# obc-v2_TMP-eMMC.net
KiCad netlist of a schematic drawn in Altium Designer
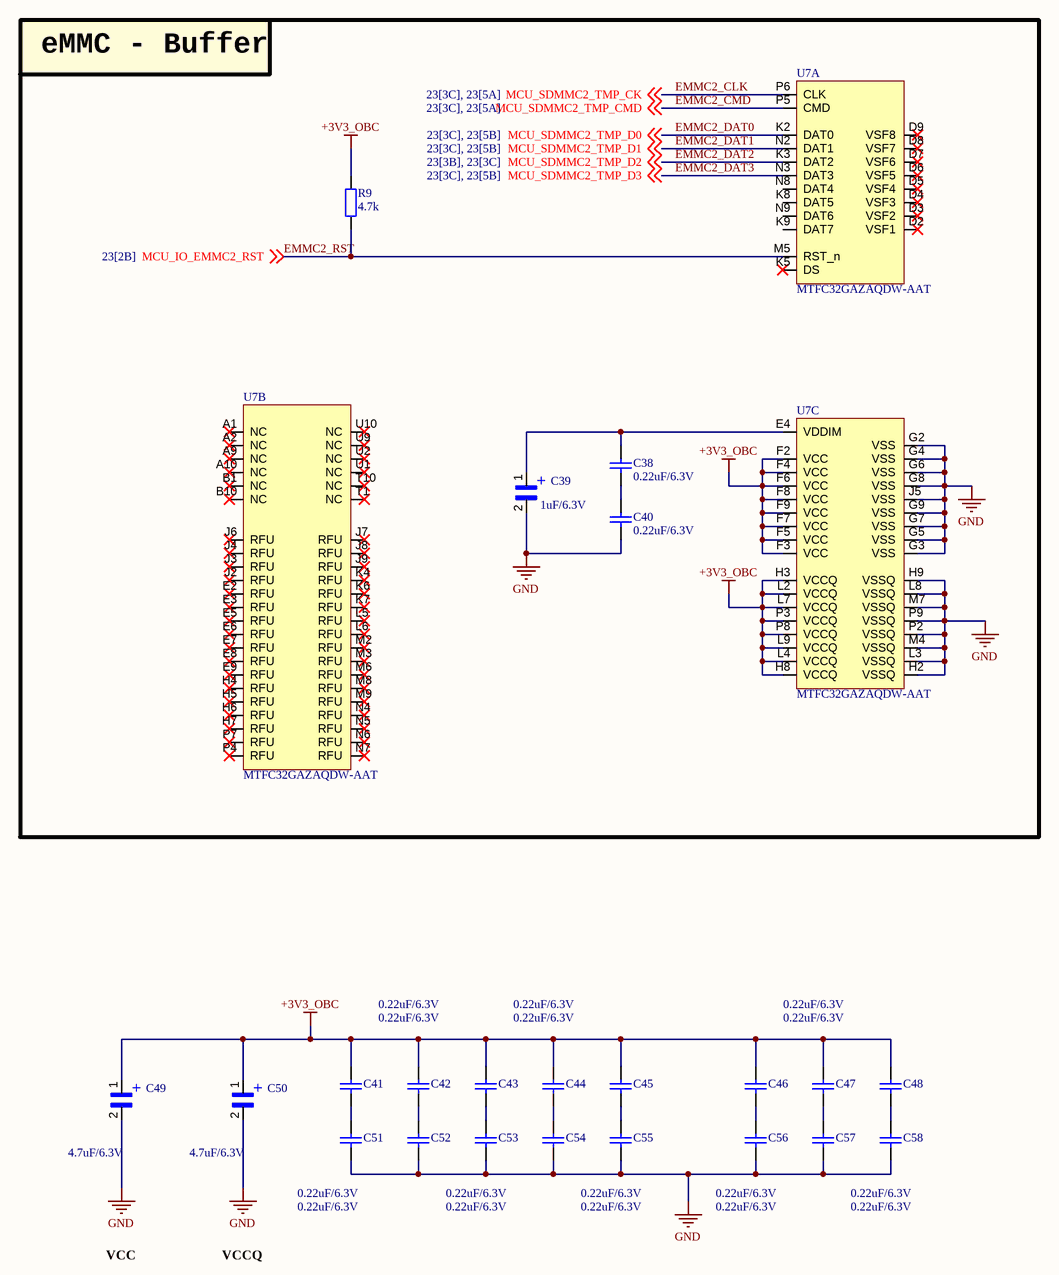
[diagram p0: obc-v2_TMP-eMMC.SchDoc]

(export (version "E")
  (design (tool "Eeschema 10.0.6"))
  (components
    (comp (ref "C38")
      (value "0.22uF/6.3V")
      (footprint "CAP_C_1005X60")
      (description "CAPC")
      (libsource (lib "Altium_Lib_by_KhueNguyenCreator") (part "Tu 0402 33nF 10V"))
    )
    (comp (ref "C39")
      (value "1uF/6.3V")
      (footprint "CAP_MP_1608X90")
      (description "CAPP")
      (fields (field (name "MP") "TACL335M003RTA"))
      (libsource (lib "TACL335M003RTA") (part "TACL335M003RTA"))
    )
    (comp (ref "C40")
      (value "0.22uF/6.3V")
      (footprint "CAP_C_1005X60")
      (description "CAPC")
      (libsource (lib "Altium_Lib_by_KhueNguyenCreator") (part "Tu 0402 33nF 10V"))
    )
    (comp (ref "C41")
      (value "0.22uF/6.3V")
      (footprint "CAP_C_1005X60")
      (description "CAPC")
      (libsource (lib "Altium_Lib_by_KhueNguyenCreator") (part "Tu 0402 33nF 10V"))
    )
    (comp (ref "C42")
      (value "0.22uF/6.3V")
      (footprint "CAP_C_1005X60")
      (description "CAPC")
      (libsource (lib "Altium_Lib_by_KhueNguyenCreator") (part "Tu 0402 33nF 10V"))
    )
    (comp (ref "C43")
      (value "0.22uF/6.3V")
      (footprint "CAP_C_1005X60")
      (description "CAPC")
      (libsource (lib "Altium_Lib_by_KhueNguyenCreator") (part "Tu 0402 33nF 10V"))
    )
    (comp (ref "C44")
      (value "0.22uF/6.3V")
      (footprint "CAP_C_1005X60")
      (description "CAPC")
      (libsource (lib "Altium_Lib_by_KhueNguyenCreator") (part "Tu 0402 33nF 10V"))
    )
    (comp (ref "C45")
      (value "0.22uF/6.3V")
      (footprint "CAP_C_1005X60")
      (description "CAPC")
      (libsource (lib "Altium_Lib_by_KhueNguyenCreator") (part "Tu 0402 33nF 10V"))
    )
    (comp (ref "C46")
      (value "0.22uF/6.3V")
      (footprint "CAP_C_1005X60")
      (description "CAPC")
      (libsource (lib "Altium_Lib_by_KhueNguyenCreator") (part "Tu 0402 33nF 10V"))
    )
    (comp (ref "C47")
      (value "0.22uF/6.3V")
      (footprint "CAP_C_1005X60")
      (description "CAPC")
      (libsource (lib "Altium_Lib_by_KhueNguyenCreator") (part "Tu 0402 33nF 10V"))
    )
    (comp (ref "C48")
      (value "0.22uF/6.3V")
      (footprint "CAP_C_1005X60")
      (description "CAPC")
      (libsource (lib "Altium_Lib_by_KhueNguyenCreator") (part "Tu 0402 33nF 10V"))
    )
    (comp (ref "C49")
      (value "4.7uF/6.3V")
      (footprint "CAP_MP_1608X90")
      (description "CAPP")
      (fields (field (name "MP") "TACL335M003RTA"))
      (libsource (lib "TACL335M003RTA") (part "TACL335M003RTA"))
    )
    (comp (ref "C50")
      (value "4.7uF/6.3V")
      (footprint "CAP_MP_1608X90")
      (description "CAPP")
      (fields (field (name "MP") "TACL335M003RTA"))
      (libsource (lib "TACL335M003RTA") (part "TACL335M003RTA"))
    )
    (comp (ref "C51")
      (value "0.22uF/6.3V")
      (footprint "CAP_C_1005X60")
      (description "CAPC")
      (libsource (lib "Altium_Lib_by_KhueNguyenCreator") (part "Tu 0402 33nF 10V"))
    )
    (comp (ref "C52")
      (value "0.22uF/6.3V")
      (footprint "CAP_C_1005X60")
      (description "CAPC")
      (libsource (lib "Altium_Lib_by_KhueNguyenCreator") (part "Tu 0402 33nF 10V"))
    )
    (comp (ref "C53")
      (value "0.22uF/6.3V")
      (footprint "CAP_C_1005X60")
      (description "CAPC")
      (libsource (lib "Altium_Lib_by_KhueNguyenCreator") (part "Tu 0402 33nF 10V"))
    )
    (comp (ref "C54")
      (value "0.22uF/6.3V")
      (footprint "CAP_C_1005X60")
      (description "CAPC")
      (libsource (lib "Altium_Lib_by_KhueNguyenCreator") (part "Tu 0402 33nF 10V"))
    )
    (comp (ref "C55")
      (value "0.22uF/6.3V")
      (footprint "CAP_C_1005X60")
      (description "CAPC")
      (libsource (lib "Altium_Lib_by_KhueNguyenCreator") (part "Tu 0402 33nF 10V"))
    )
    (comp (ref "C56")
      (value "0.22uF/6.3V")
      (footprint "CAP_C_1005X60")
      (description "CAPC")
      (libsource (lib "Altium_Lib_by_KhueNguyenCreator") (part "Tu 0402 33nF 10V"))
    )
    (comp (ref "C57")
      (value "0.22uF/6.3V")
      (footprint "CAP_C_1005X60")
      (description "CAPC")
      (libsource (lib "Altium_Lib_by_KhueNguyenCreator") (part "Tu 0402 33nF 10V"))
    )
    (comp (ref "C58")
      (value "0.22uF/6.3V")
      (footprint "CAP_C_1005X60")
      (description "CAPC")
      (libsource (lib "Altium_Lib_by_KhueNguyenCreator") (part "Tu 0402 33nF 10V"))
    )
    (comp (ref "R9")
      (value "4.7k")
      (footprint "RES_C_1608X60")
      (description "RES")
      (libsource (lib "Altium_Lib_by_KhueNguyenCreator") (part "Tro 0603 1% 10k"))
    )
    (comp (ref "U7")
      (value "MTFC32GAZAQDW-AAT")
      (footprint "BGA_100_C_100P_10X17_1400X1800X150")
      (libsource (lib "emmc_nofootprint") (part "MTFC32GAZAQDW-AAT"))
    )
  )
  (nets
    (net (code "1") (name "+3V3_OBC") (class "Default")
      (node (ref "C41") (pin "1") (pinfunction "1_1") (pintype "passive"))
      (node (ref "C42") (pin "1") (pinfunction "1_1") (pintype "passive"))
      (node (ref "C43") (pin "1") (pinfunction "1_1") (pintype "passive"))
      (node (ref "C44") (pin "1") (pinfunction "1_1") (pintype "passive"))
      (node (ref "C45") (pin "1") (pinfunction "1_1") (pintype "passive"))
      (node (ref "C46") (pin "1") (pinfunction "1_1") (pintype "passive"))
      (node (ref "C47") (pin "1") (pinfunction "1_1") (pintype "passive"))
      (node (ref "C48") (pin "1") (pinfunction "1_1") (pintype "passive"))
      (node (ref "C49") (pin "1") (pinfunction "1_1") (pintype "passive"))
      (node (ref "C50") (pin "1") (pinfunction "1_1") (pintype "passive"))
      (node (ref "R9") (pin "1") (pinfunction "1_1") (pintype "passive"))
      (node (ref "U7") (pin "F2") (pinfunction "VCC_F2") (pintype "passive"))
      (node (ref "U7") (pin "F3") (pinfunction "VCC_F3") (pintype "passive"))
      (node (ref "U7") (pin "F4") (pinfunction "VCC_F4") (pintype "passive"))
      (node (ref "U7") (pin "F5") (pinfunction "VCC_F5") (pintype "passive"))
      (node (ref "U7") (pin "F6") (pinfunction "VCC_F6") (pintype "passive"))
      (node (ref "U7") (pin "F7") (pinfunction "VCC_F7") (pintype "passive"))
      (node (ref "U7") (pin "F8") (pinfunction "VCC_F8") (pintype "passive"))
      (node (ref "U7") (pin "F9") (pinfunction "VCC_F9") (pintype "passive"))
      (node (ref "U7") (pin "H3") (pinfunction "VCCQ_H3") (pintype "passive"))
      (node (ref "U7") (pin "H8") (pinfunction "VCCQ_H8") (pintype "passive"))
      (node (ref "U7") (pin "L2") (pinfunction "VCCQ_L2") (pintype "passive"))
      (node (ref "U7") (pin "L4") (pinfunction "VCCQ_L4") (pintype "passive"))
      (node (ref "U7") (pin "L7") (pinfunction "VCCQ_L7") (pintype "passive"))
      (node (ref "U7") (pin "L9") (pinfunction "VCCQ_L9") (pintype "passive"))
      (node (ref "U7") (pin "P3") (pinfunction "VCCQ_P3") (pintype "passive"))
      (node (ref "U7") (pin "P8") (pinfunction "VCCQ_P8") (pintype "passive"))
    )
    (net (code "2") (name "GND") (class "Default")
      (node (ref "C39") (pin "2") (pinfunction "2_2") (pintype "passive"))
      (node (ref "C40") (pin "2") (pinfunction "2_2") (pintype "passive"))
      (node (ref "C49") (pin "2") (pinfunction "2_2") (pintype "passive"))
      (node (ref "C50") (pin "2") (pinfunction "2_2") (pintype "passive"))
      (node (ref "C51") (pin "2") (pinfunction "2_2") (pintype "passive"))
      (node (ref "C52") (pin "2") (pinfunction "2_2") (pintype "passive"))
      (node (ref "C53") (pin "2") (pinfunction "2_2") (pintype "passive"))
      (node (ref "C54") (pin "2") (pinfunction "2_2") (pintype "passive"))
      (node (ref "C55") (pin "2") (pinfunction "2_2") (pintype "passive"))
      (node (ref "C56") (pin "2") (pinfunction "2_2") (pintype "passive"))
      (node (ref "C57") (pin "2") (pinfunction "2_2") (pintype "passive"))
      (node (ref "C58") (pin "2") (pinfunction "2_2") (pintype "passive"))
      (node (ref "U7") (pin "G2") (pinfunction "VSS_G2") (pintype "passive"))
      (node (ref "U7") (pin "G3") (pinfunction "VSS_G3") (pintype "passive"))
      (node (ref "U7") (pin "G4") (pinfunction "VSS_G4") (pintype "passive"))
      (node (ref "U7") (pin "G5") (pinfunction "VSS_G5") (pintype "passive"))
      (node (ref "U7") (pin "G6") (pinfunction "VSS_G6") (pintype "passive"))
      (node (ref "U7") (pin "G7") (pinfunction "VSS_G7") (pintype "passive"))
      (node (ref "U7") (pin "G8") (pinfunction "VSS_G8") (pintype "passive"))
      (node (ref "U7") (pin "G9") (pinfunction "VSS_G9") (pintype "passive"))
      (node (ref "U7") (pin "H2") (pinfunction "VSSQ_H2") (pintype "passive"))
      (node (ref "U7") (pin "H9") (pinfunction "VSSQ_H9") (pintype "passive"))
      (node (ref "U7") (pin "J5") (pinfunction "VSS_J5") (pintype "passive"))
      (node (ref "U7") (pin "L3") (pinfunction "VSSQ_L3") (pintype "passive"))
      (node (ref "U7") (pin "L8") (pinfunction "VSSQ_L8") (pintype "passive"))
      (node (ref "U7") (pin "M4") (pinfunction "VSSQ_M4") (pintype "passive"))
      (node (ref "U7") (pin "M7") (pinfunction "VSSQ_M7") (pintype "passive"))
      (node (ref "U7") (pin "P2") (pinfunction "VSSQ_P2") (pintype "passive"))
      (node (ref "U7") (pin "P9") (pinfunction "VSSQ_P9") (pintype "passive"))
    )
    (net (code "3") (name "MCU_IO_EMMC2_RST") (class "Default")
      (node (ref "R9") (pin "2") (pinfunction "2_2") (pintype "passive"))
      (node (ref "U7") (pin "M5") (pinfunction "RST_n_M5") (pintype "passive"))
    )
    (net (code "4") (name "MCU_SDMMC2_TMP_CK") (class "Default")
      (node (ref "U7") (pin "P6") (pinfunction "CLK_P6") (pintype "passive"))
    )
    (net (code "5") (name "MCU_SDMMC2_TMP_CMD") (class "Default")
      (node (ref "U7") (pin "P5") (pinfunction "CMD_P5") (pintype "passive"))
    )
    (net (code "6") (name "MCU_SDMMC2_TMP_D0") (class "Default")
      (node (ref "U7") (pin "K2") (pinfunction "DAT0_K2") (pintype "passive"))
    )
    (net (code "7") (name "MCU_SDMMC2_TMP_D1") (class "Default")
      (node (ref "U7") (pin "N2") (pinfunction "DAT1_N2") (pintype "passive"))
    )
    (net (code "8") (name "MCU_SDMMC2_TMP_D2") (class "Default")
      (node (ref "U7") (pin "K3") (pinfunction "DAT2_K3") (pintype "passive"))
    )
    (net (code "9") (name "MCU_SDMMC2_TMP_D3") (class "Default")
      (node (ref "U7") (pin "N3") (pinfunction "DAT3_N3") (pintype "passive"))
    )
    (net (code "10") (name "Net-(C38-Pad2)") (class "Default")
      (node (ref "C38") (pin "2") (pinfunction "2_2") (pintype "passive"))
      (node (ref "C40") (pin "1") (pinfunction "1_1") (pintype "passive"))
    )
    (net (code "11") (name "Net-(C41-Pad2)") (class "Default")
      (node (ref "C41") (pin "2") (pinfunction "2_2") (pintype "passive"))
      (node (ref "C51") (pin "1") (pinfunction "1_1") (pintype "passive"))
    )
    (net (code "12") (name "Net-(C42-Pad2)") (class "Default")
      (node (ref "C42") (pin "2") (pinfunction "2_2") (pintype "passive"))
      (node (ref "C52") (pin "1") (pinfunction "1_1") (pintype "passive"))
    )
    (net (code "13") (name "Net-(C43-Pad2)") (class "Default")
      (node (ref "C43") (pin "2") (pinfunction "2_2") (pintype "passive"))
      (node (ref "C53") (pin "1") (pinfunction "1_1") (pintype "passive"))
    )
    (net (code "14") (name "Net-(C44-Pad2)") (class "Default")
      (node (ref "C44") (pin "2") (pinfunction "2_2") (pintype "passive"))
      (node (ref "C54") (pin "1") (pinfunction "1_1") (pintype "passive"))
    )
    (net (code "15") (name "Net-(C45-Pad2)") (class "Default")
      (node (ref "C45") (pin "2") (pinfunction "2_2") (pintype "passive"))
      (node (ref "C55") (pin "1") (pinfunction "1_1") (pintype "passive"))
    )
    (net (code "16") (name "Net-(C46-Pad2)") (class "Default")
      (node (ref "C46") (pin "2") (pinfunction "2_2") (pintype "passive"))
      (node (ref "C56") (pin "1") (pinfunction "1_1") (pintype "passive"))
    )
    (net (code "17") (name "Net-(C47-Pad2)") (class "Default")
      (node (ref "C47") (pin "2") (pinfunction "2_2") (pintype "passive"))
      (node (ref "C57") (pin "1") (pinfunction "1_1") (pintype "passive"))
    )
    (net (code "18") (name "Net-(C48-Pad2)") (class "Default")
      (node (ref "C48") (pin "2") (pinfunction "2_2") (pintype "passive"))
      (node (ref "C58") (pin "1") (pinfunction "1_1") (pintype "passive"))
    )
    (net (code "19") (name "Net-(U7C-VDDIM)") (class "Default")
      (node (ref "C38") (pin "1") (pinfunction "1_1") (pintype "passive"))
      (node (ref "C39") (pin "1") (pinfunction "1_1") (pintype "passive"))
      (node (ref "U7") (pin "E4") (pinfunction "VDDIM_E4") (pintype "passive"))
    )
    (net (code "20") (name "unconnected-(U7A-DAT4-PadN8)") (class "Default")
      (node (ref "U7") (pin "N8") (pinfunction "DAT4_N8") (pintype "passive"))
    )
    (net (code "21") (name "unconnected-(U7A-DAT5-PadK8)") (class "Default")
      (node (ref "U7") (pin "K8") (pinfunction "DAT5_K8") (pintype "passive"))
    )
    (net (code "22") (name "unconnected-(U7A-DAT6-PadN9)") (class "Default")
      (node (ref "U7") (pin "N9") (pinfunction "DAT6_N9") (pintype "passive"))
    )
    (net (code "23") (name "unconnected-(U7A-DAT7-PadK9)") (class "Default")
      (node (ref "U7") (pin "K9") (pinfunction "DAT7_K9") (pintype "passive"))
    )
    (net (code "24") (name "unconnected-(U7A-DS-PadK5)") (class "Default")
      (node (ref "U7") (pin "K5") (pinfunction "DS_K5") (pintype "passive+no_connect"))
    )
    (net (code "25") (name "unconnected-(U7A-VSF1-PadD2)") (class "Default")
      (node (ref "U7") (pin "D2") (pinfunction "VSF1_D2") (pintype "passive+no_connect"))
    )
    (net (code "26") (name "unconnected-(U7A-VSF2-PadD3)") (class "Default")
      (node (ref "U7") (pin "D3") (pinfunction "VSF2_D3") (pintype "passive+no_connect"))
    )
    (net (code "27") (name "unconnected-(U7A-VSF3-PadD4)") (class "Default")
      (node (ref "U7") (pin "D4") (pinfunction "VSF3_D4") (pintype "passive+no_connect"))
    )
    (net (code "28") (name "unconnected-(U7A-VSF4-PadD5)") (class "Default")
      (node (ref "U7") (pin "D5") (pinfunction "VSF4_D5") (pintype "passive+no_connect"))
    )
    (net (code "29") (name "unconnected-(U7A-VSF5-PadD6)") (class "Default")
      (node (ref "U7") (pin "D6") (pinfunction "VSF5_D6") (pintype "passive+no_connect"))
    )
    (net (code "30") (name "unconnected-(U7A-VSF6-PadD7)") (class "Default")
      (node (ref "U7") (pin "D7") (pinfunction "VSF6_D7") (pintype "passive+no_connect"))
    )
    (net (code "31") (name "unconnected-(U7A-VSF7-PadD8)") (class "Default")
      (node (ref "U7") (pin "D8") (pinfunction "VSF7_D8") (pintype "passive+no_connect"))
    )
    (net (code "32") (name "unconnected-(U7A-VSF8-PadD9)") (class "Default")
      (node (ref "U7") (pin "D9") (pinfunction "VSF8_D9") (pintype "passive+no_connect"))
    )
    (net (code "33") (name "unconnected-(U7B-NC-PadA1)") (class "Default")
      (node (ref "U7") (pin "A1") (pinfunction "NC_A1") (pintype "passive+no_connect"))
    )
    (net (code "34") (name "unconnected-(U7B-NC-PadA2)") (class "Default")
      (node (ref "U7") (pin "A2") (pinfunction "NC_A2") (pintype "passive+no_connect"))
    )
    (net (code "35") (name "unconnected-(U7B-NC-PadA9)") (class "Default")
      (node (ref "U7") (pin "A9") (pinfunction "NC_A9") (pintype "passive+no_connect"))
    )
    (net (code "36") (name "unconnected-(U7B-NC-PadA10)") (class "Default")
      (node (ref "U7") (pin "A10") (pinfunction "NC_A10") (pintype "passive+no_connect"))
    )
    (net (code "37") (name "unconnected-(U7B-NC-PadB1)") (class "Default")
      (node (ref "U7") (pin "B1") (pinfunction "NC_B1") (pintype "passive+no_connect"))
    )
    (net (code "38") (name "unconnected-(U7B-NC-PadB10)") (class "Default")
      (node (ref "U7") (pin "B10") (pinfunction "NC_B10") (pintype "passive+no_connect"))
    )
    (net (code "39") (name "unconnected-(U7B-NC-PadT1)") (class "Default")
      (node (ref "U7") (pin "T1") (pinfunction "NC_T1") (pintype "passive+no_connect"))
    )
    (net (code "40") (name "unconnected-(U7B-NC-PadT10)") (class "Default")
      (node (ref "U7") (pin "T10") (pinfunction "NC_T10") (pintype "passive+no_connect"))
    )
    (net (code "41") (name "unconnected-(U7B-NC-PadU1)") (class "Default")
      (node (ref "U7") (pin "U1") (pinfunction "NC_U1") (pintype "passive+no_connect"))
    )
    (net (code "42") (name "unconnected-(U7B-NC-PadU2)") (class "Default")
      (node (ref "U7") (pin "U2") (pinfunction "NC_U2") (pintype "passive+no_connect"))
    )
    (net (code "43") (name "unconnected-(U7B-NC-PadU9)") (class "Default")
      (node (ref "U7") (pin "U9") (pinfunction "NC_U9") (pintype "passive+no_connect"))
    )
    (net (code "44") (name "unconnected-(U7B-NC-PadU10)") (class "Default")
      (node (ref "U7") (pin "U10") (pinfunction "NC_U10") (pintype "passive+no_connect"))
    )
    (net (code "45") (name "unconnected-(U7B-RFU-PadE2)") (class "Default")
      (node (ref "U7") (pin "E2") (pinfunction "RFU_E2") (pintype "passive+no_connect"))
    )
    (net (code "46") (name "unconnected-(U7B-RFU-PadE3)") (class "Default")
      (node (ref "U7") (pin "E3") (pinfunction "RFU_E3") (pintype "passive+no_connect"))
    )
    (net (code "47") (name "unconnected-(U7B-RFU-PadE5)") (class "Default")
      (node (ref "U7") (pin "E5") (pinfunction "RFU_E5") (pintype "passive+no_connect"))
    )
    (net (code "48") (name "unconnected-(U7B-RFU-PadE6)") (class "Default")
      (node (ref "U7") (pin "E6") (pinfunction "RFU_E6") (pintype "passive+no_connect"))
    )
    (net (code "49") (name "unconnected-(U7B-RFU-PadE7)") (class "Default")
      (node (ref "U7") (pin "E7") (pinfunction "RFU_E7") (pintype "passive+no_connect"))
    )
    (net (code "50") (name "unconnected-(U7B-RFU-PadE8)") (class "Default")
      (node (ref "U7") (pin "E8") (pinfunction "RFU_E8") (pintype "passive+no_connect"))
    )
    (net (code "51") (name "unconnected-(U7B-RFU-PadE9)") (class "Default")
      (node (ref "U7") (pin "E9") (pinfunction "RFU_E9") (pintype "passive+no_connect"))
    )
    (net (code "52") (name "unconnected-(U7B-RFU-PadH4)") (class "Default")
      (node (ref "U7") (pin "H4") (pinfunction "RFU_H4") (pintype "passive+no_connect"))
    )
    (net (code "53") (name "unconnected-(U7B-RFU-PadH5)") (class "Default")
      (node (ref "U7") (pin "H5") (pinfunction "RFU_H5") (pintype "passive+no_connect"))
    )
    (net (code "54") (name "unconnected-(U7B-RFU-PadH6)") (class "Default")
      (node (ref "U7") (pin "H6") (pinfunction "RFU_H6") (pintype "passive+no_connect"))
    )
    (net (code "55") (name "unconnected-(U7B-RFU-PadH7)") (class "Default")
      (node (ref "U7") (pin "H7") (pinfunction "RFU_H7") (pintype "passive+no_connect"))
    )
    (net (code "56") (name "unconnected-(U7B-RFU-PadJ2)") (class "Default")
      (node (ref "U7") (pin "J2") (pinfunction "RFU_J2") (pintype "passive+no_connect"))
    )
    (net (code "57") (name "unconnected-(U7B-RFU-PadJ3)") (class "Default")
      (node (ref "U7") (pin "J3") (pinfunction "RFU_J3") (pintype "passive+no_connect"))
    )
    (net (code "58") (name "unconnected-(U7B-RFU-PadJ4)") (class "Default")
      (node (ref "U7") (pin "J4") (pinfunction "RFU_J4") (pintype "passive+no_connect"))
    )
    (net (code "59") (name "unconnected-(U7B-RFU-PadJ6)") (class "Default")
      (node (ref "U7") (pin "J6") (pinfunction "RFU_J6") (pintype "passive+no_connect"))
    )
    (net (code "60") (name "unconnected-(U7B-RFU-PadJ7)") (class "Default")
      (node (ref "U7") (pin "J7") (pinfunction "RFU_J7") (pintype "passive+no_connect"))
    )
    (net (code "61") (name "unconnected-(U7B-RFU-PadJ8)") (class "Default")
      (node (ref "U7") (pin "J8") (pinfunction "RFU_J8") (pintype "passive+no_connect"))
    )
    (net (code "62") (name "unconnected-(U7B-RFU-PadJ9)") (class "Default")
      (node (ref "U7") (pin "J9") (pinfunction "RFU_J9") (pintype "passive+no_connect"))
    )
    (net (code "63") (name "unconnected-(U7B-RFU-PadK4)") (class "Default")
      (node (ref "U7") (pin "K4") (pinfunction "RFU_K4") (pintype "passive+no_connect"))
    )
    (net (code "64") (name "unconnected-(U7B-RFU-PadK6)") (class "Default")
      (node (ref "U7") (pin "K6") (pinfunction "RFU_K6") (pintype "passive+no_connect"))
    )
    (net (code "65") (name "unconnected-(U7B-RFU-PadK7)") (class "Default")
      (node (ref "U7") (pin "K7") (pinfunction "RFU_K7") (pintype "passive+no_connect"))
    )
    (net (code "66") (name "unconnected-(U7B-RFU-PadL5)") (class "Default")
      (node (ref "U7") (pin "L5") (pinfunction "RFU_L5") (pintype "passive+no_connect"))
    )
    (net (code "67") (name "unconnected-(U7B-RFU-PadL6)") (class "Default")
      (node (ref "U7") (pin "L6") (pinfunction "RFU_L6") (pintype "passive+no_connect"))
    )
    (net (code "68") (name "unconnected-(U7B-RFU-PadM2)") (class "Default")
      (node (ref "U7") (pin "M2") (pinfunction "RFU_M2") (pintype "passive+no_connect"))
    )
    (net (code "69") (name "unconnected-(U7B-RFU-PadM3)") (class "Default")
      (node (ref "U7") (pin "M3") (pinfunction "RFU_M3") (pintype "passive+no_connect"))
    )
    (net (code "70") (name "unconnected-(U7B-RFU-PadM6)") (class "Default")
      (node (ref "U7") (pin "M6") (pinfunction "RFU_M6") (pintype "passive+no_connect"))
    )
    (net (code "71") (name "unconnected-(U7B-RFU-PadM8)") (class "Default")
      (node (ref "U7") (pin "M8") (pinfunction "RFU_M8") (pintype "passive+no_connect"))
    )
    (net (code "72") (name "unconnected-(U7B-RFU-PadM9)") (class "Default")
      (node (ref "U7") (pin "M9") (pinfunction "RFU_M9") (pintype "passive+no_connect"))
    )
    (net (code "73") (name "unconnected-(U7B-RFU-PadN4)") (class "Default")
      (node (ref "U7") (pin "N4") (pinfunction "RFU_N4") (pintype "passive+no_connect"))
    )
    (net (code "74") (name "unconnected-(U7B-RFU-PadN5)") (class "Default")
      (node (ref "U7") (pin "N5") (pinfunction "RFU_N5") (pintype "passive+no_connect"))
    )
    (net (code "75") (name "unconnected-(U7B-RFU-PadN6)") (class "Default")
      (node (ref "U7") (pin "N6") (pinfunction "RFU_N6") (pintype "passive+no_connect"))
    )
    (net (code "76") (name "unconnected-(U7B-RFU-PadN7)") (class "Default")
      (node (ref "U7") (pin "N7") (pinfunction "RFU_N7") (pintype "passive+no_connect"))
    )
    (net (code "77") (name "unconnected-(U7B-RFU-PadP4)") (class "Default")
      (node (ref "U7") (pin "P4") (pinfunction "RFU_P4") (pintype "passive+no_connect"))
    )
    (net (code "78") (name "unconnected-(U7B-RFU-PadP7)") (class "Default")
      (node (ref "U7") (pin "P7") (pinfunction "RFU_P7") (pintype "passive+no_connect"))
    )
  )
)
